# Adapterplatine_v1_2.net
KiCad netlist of a schematic drawn in EAGLE
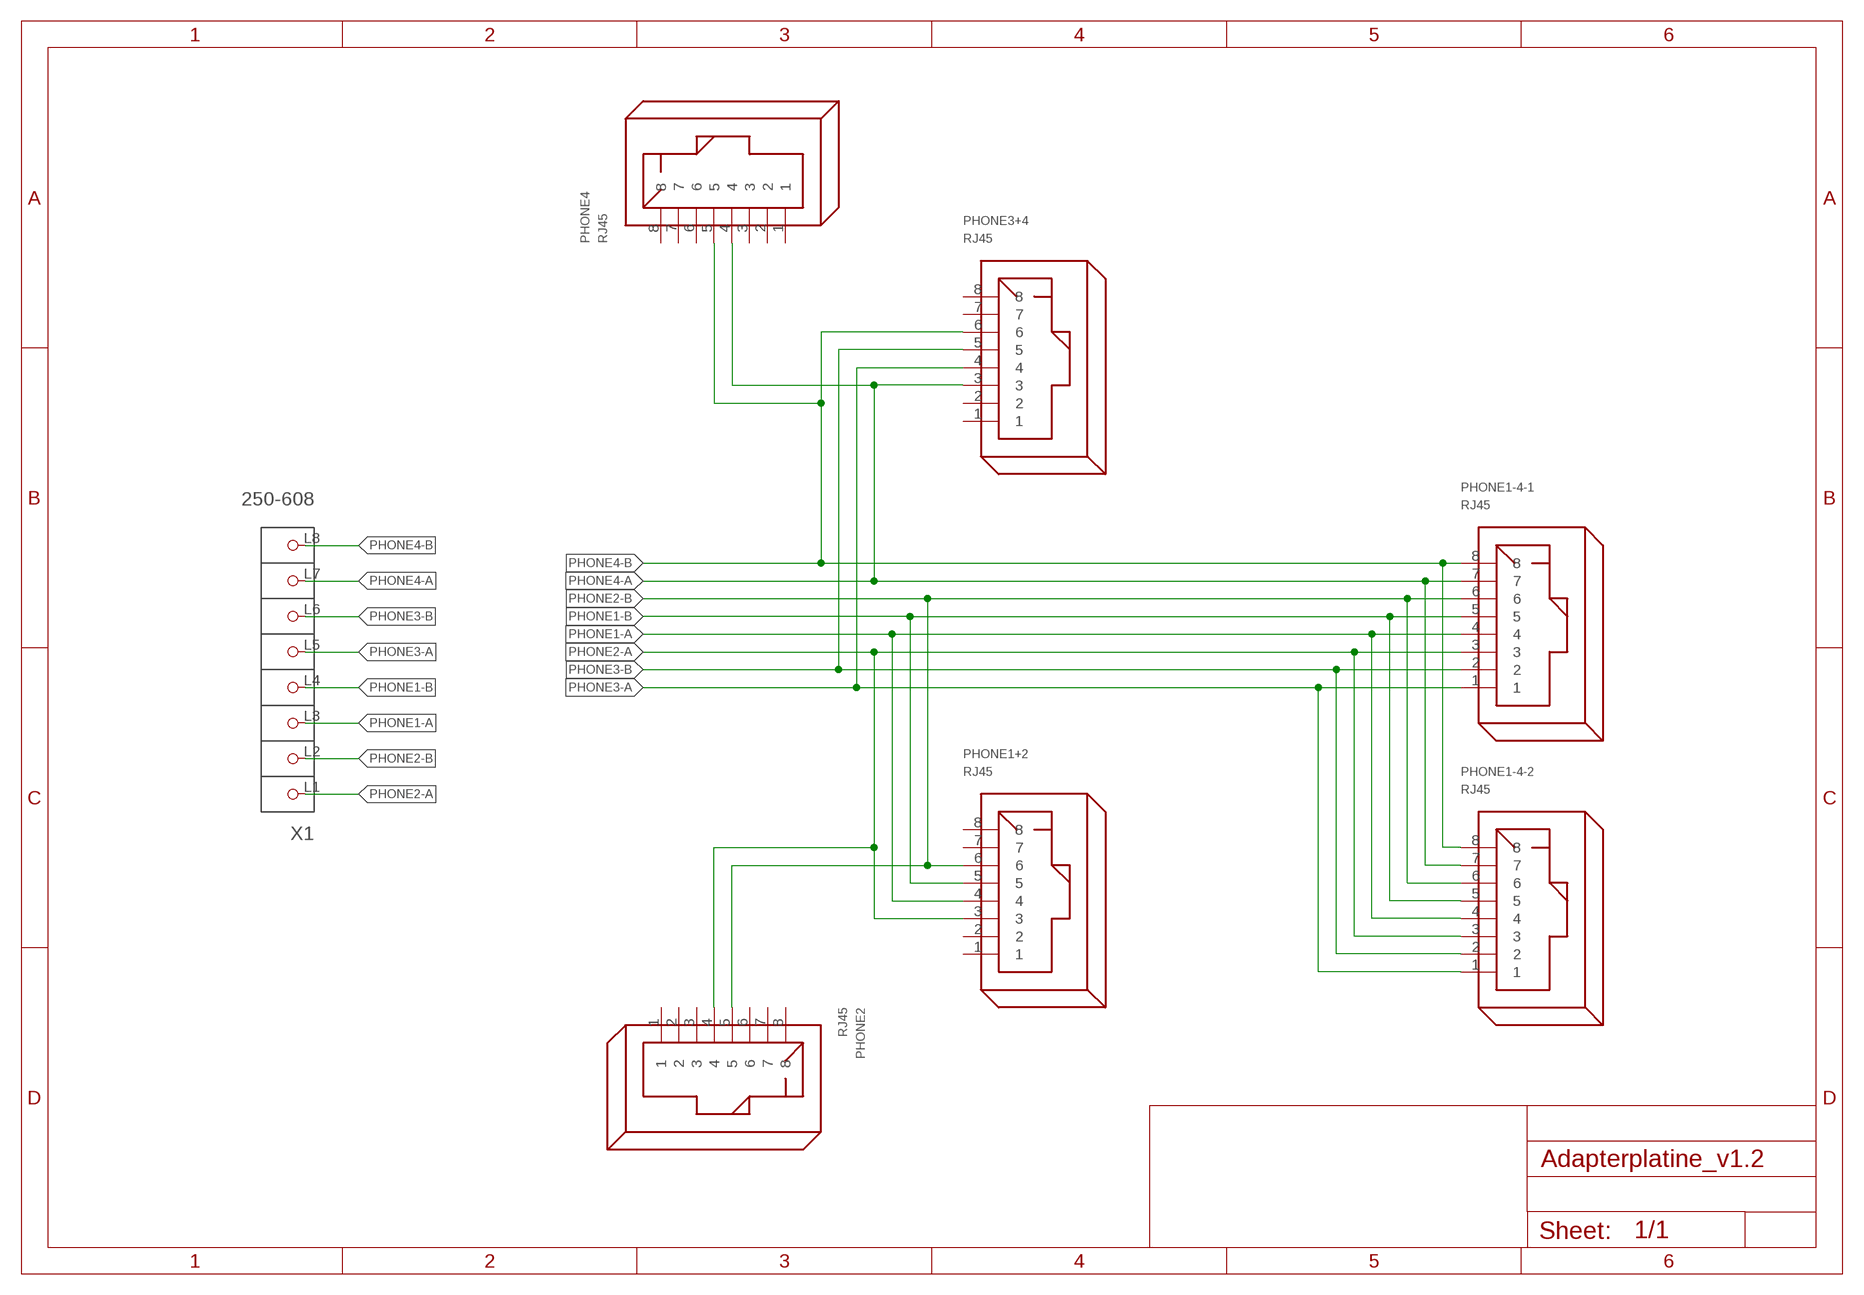
[diagram p0: schematic, sheet 1]

(export (version "E")
  (design (tool "Eeschema 10.0.6"))
  (components
    (comp (ref "PHONE1+2")
      (value "RJ45")
      (footprint "eagle-import:RJ45")
      (libsource (lib "eagle-import") (part "RJ45"))
    )
    (comp (ref "PHONE1-4-1")
      (value "RJ45")
      (footprint "eagle-import:RJ45")
      (libsource (lib "eagle-import") (part "RJ45"))
    )
    (comp (ref "PHONE1-4-2")
      (value "RJ45")
      (footprint "eagle-import:RJ45")
      (libsource (lib "eagle-import") (part "RJ45"))
    )
    (comp (ref "PHONE2")
      (value "RJ45")
      (footprint "eagle-import:RJ45")
      (libsource (lib "eagle-import") (part "RJ45"))
    )
    (comp (ref "PHONE3+4")
      (value "RJ45")
      (footprint "eagle-import:RJ45")
      (libsource (lib "eagle-import") (part "RJ45"))
    )
    (comp (ref "PHONE4")
      (value "RJ45")
      (footprint "eagle-import:RJ45")
      (libsource (lib "eagle-import") (part "RJ45"))
    )
    (comp (ref "X1")
      (value "250-608")
      (footprint "eagle-import:P-250-608")
      (libsource (lib "eagle-import") (part "250-608"))
    )
  )
  (nets
    (net (code "1") (name "PHONE1-A") (class "Default")
      (node (ref "PHONE1+2") (pin "4") (pinfunction "4_4") (pintype "bidirectional"))
      (node (ref "PHONE1-4-1") (pin "4") (pinfunction "4_4") (pintype "bidirectional"))
      (node (ref "PHONE1-4-2") (pin "4") (pinfunction "4_4") (pintype "bidirectional"))
      (node (ref "X1") (pin "L3") (pinfunction "P3_L3") (pintype "bidirectional"))
    )
    (net (code "2") (name "PHONE1-B") (class "Default")
      (node (ref "PHONE1+2") (pin "5") (pinfunction "5_5") (pintype "bidirectional"))
      (node (ref "PHONE1-4-1") (pin "5") (pinfunction "5_5") (pintype "bidirectional"))
      (node (ref "PHONE1-4-2") (pin "5") (pinfunction "5_5") (pintype "bidirectional"))
      (node (ref "X1") (pin "L4") (pinfunction "P4_L4") (pintype "bidirectional"))
    )
    (net (code "3") (name "PHONE2-A") (class "Default")
      (node (ref "PHONE1+2") (pin "3") (pinfunction "3_3") (pintype "bidirectional"))
      (node (ref "PHONE1-4-1") (pin "3") (pinfunction "3_3") (pintype "bidirectional"))
      (node (ref "PHONE1-4-2") (pin "3") (pinfunction "3_3") (pintype "bidirectional"))
      (node (ref "PHONE2") (pin "4") (pinfunction "4_4") (pintype "bidirectional"))
      (node (ref "X1") (pin "L1") (pinfunction "P1_L1") (pintype "bidirectional"))
    )
    (net (code "4") (name "PHONE2-B") (class "Default")
      (node (ref "PHONE1+2") (pin "6") (pinfunction "6_6") (pintype "bidirectional"))
      (node (ref "PHONE1-4-1") (pin "6") (pinfunction "6_6") (pintype "bidirectional"))
      (node (ref "PHONE1-4-2") (pin "6") (pinfunction "6_6") (pintype "bidirectional"))
      (node (ref "PHONE2") (pin "5") (pinfunction "5_5") (pintype "bidirectional"))
      (node (ref "X1") (pin "L2") (pinfunction "P2_L2") (pintype "bidirectional"))
    )
    (net (code "5") (name "PHONE3-A") (class "Default")
      (node (ref "PHONE1-4-1") (pin "1") (pinfunction "1_1") (pintype "bidirectional"))
      (node (ref "PHONE1-4-2") (pin "1") (pinfunction "1_1") (pintype "bidirectional"))
      (node (ref "PHONE3+4") (pin "4") (pinfunction "4_4") (pintype "bidirectional"))
      (node (ref "X1") (pin "L5") (pinfunction "P5_L5") (pintype "bidirectional"))
    )
    (net (code "6") (name "PHONE3-B") (class "Default")
      (node (ref "PHONE1-4-1") (pin "2") (pinfunction "2_2") (pintype "bidirectional"))
      (node (ref "PHONE1-4-2") (pin "2") (pinfunction "2_2") (pintype "bidirectional"))
      (node (ref "PHONE3+4") (pin "5") (pinfunction "5_5") (pintype "bidirectional"))
      (node (ref "X1") (pin "L6") (pinfunction "P6_L6") (pintype "bidirectional"))
    )
    (net (code "7") (name "PHONE4-A") (class "Default")
      (node (ref "PHONE1-4-1") (pin "7") (pinfunction "7_7") (pintype "bidirectional"))
      (node (ref "PHONE1-4-2") (pin "7") (pinfunction "7_7") (pintype "bidirectional"))
      (node (ref "PHONE3+4") (pin "3") (pinfunction "3_3") (pintype "bidirectional"))
      (node (ref "PHONE4") (pin "4") (pinfunction "4_4") (pintype "bidirectional"))
      (node (ref "X1") (pin "L7") (pinfunction "P7_L7") (pintype "bidirectional"))
    )
    (net (code "8") (name "PHONE4-B") (class "Default")
      (node (ref "PHONE1-4-1") (pin "8") (pinfunction "8_8") (pintype "bidirectional"))
      (node (ref "PHONE1-4-2") (pin "8") (pinfunction "8_8") (pintype "bidirectional"))
      (node (ref "PHONE3+4") (pin "6") (pinfunction "6_6") (pintype "bidirectional"))
      (node (ref "PHONE4") (pin "5") (pinfunction "5_5") (pintype "bidirectional"))
      (node (ref "X1") (pin "L8") (pinfunction "P8_L8") (pintype "bidirectional"))
    )
    (net (code "9") (name "unconnected-(PHONE1+2-Pad1)") (class "Default")
      (node (ref "PHONE1+2") (pin "1") (pinfunction "1_1") (pintype "bidirectional"))
    )
    (net (code "10") (name "unconnected-(PHONE1+2-Pad2)") (class "Default")
      (node (ref "PHONE1+2") (pin "2") (pinfunction "2_2") (pintype "bidirectional"))
    )
    (net (code "11") (name "unconnected-(PHONE1+2-Pad7)") (class "Default")
      (node (ref "PHONE1+2") (pin "7") (pinfunction "7_7") (pintype "bidirectional"))
    )
    (net (code "12") (name "unconnected-(PHONE1+2-Pad8)") (class "Default")
      (node (ref "PHONE1+2") (pin "8") (pinfunction "8_8") (pintype "bidirectional"))
    )
    (net (code "13") (name "unconnected-(PHONE2-Pad1)") (class "Default")
      (node (ref "PHONE2") (pin "1") (pinfunction "1_1") (pintype "bidirectional"))
    )
    (net (code "14") (name "unconnected-(PHONE2-Pad2)") (class "Default")
      (node (ref "PHONE2") (pin "2") (pinfunction "2_2") (pintype "bidirectional"))
    )
    (net (code "15") (name "unconnected-(PHONE2-Pad3)") (class "Default")
      (node (ref "PHONE2") (pin "3") (pinfunction "3_3") (pintype "bidirectional"))
    )
    (net (code "16") (name "unconnected-(PHONE2-Pad6)") (class "Default")
      (node (ref "PHONE2") (pin "6") (pinfunction "6_6") (pintype "bidirectional"))
    )
    (net (code "17") (name "unconnected-(PHONE2-Pad7)") (class "Default")
      (node (ref "PHONE2") (pin "7") (pinfunction "7_7") (pintype "bidirectional"))
    )
    (net (code "18") (name "unconnected-(PHONE2-Pad8)") (class "Default")
      (node (ref "PHONE2") (pin "8") (pinfunction "8_8") (pintype "bidirectional"))
    )
    (net (code "19") (name "unconnected-(PHONE3+4-Pad1)") (class "Default")
      (node (ref "PHONE3+4") (pin "1") (pinfunction "1_1") (pintype "bidirectional"))
    )
    (net (code "20") (name "unconnected-(PHONE3+4-Pad2)") (class "Default")
      (node (ref "PHONE3+4") (pin "2") (pinfunction "2_2") (pintype "bidirectional"))
    )
    (net (code "21") (name "unconnected-(PHONE3+4-Pad7)") (class "Default")
      (node (ref "PHONE3+4") (pin "7") (pinfunction "7_7") (pintype "bidirectional"))
    )
    (net (code "22") (name "unconnected-(PHONE3+4-Pad8)") (class "Default")
      (node (ref "PHONE3+4") (pin "8") (pinfunction "8_8") (pintype "bidirectional"))
    )
    (net (code "23") (name "unconnected-(PHONE4-Pad1)") (class "Default")
      (node (ref "PHONE4") (pin "1") (pinfunction "1_1") (pintype "bidirectional"))
    )
    (net (code "24") (name "unconnected-(PHONE4-Pad2)") (class "Default")
      (node (ref "PHONE4") (pin "2") (pinfunction "2_2") (pintype "bidirectional"))
    )
    (net (code "25") (name "unconnected-(PHONE4-Pad3)") (class "Default")
      (node (ref "PHONE4") (pin "3") (pinfunction "3_3") (pintype "bidirectional"))
    )
    (net (code "26") (name "unconnected-(PHONE4-Pad6)") (class "Default")
      (node (ref "PHONE4") (pin "6") (pinfunction "6_6") (pintype "bidirectional"))
    )
    (net (code "27") (name "unconnected-(PHONE4-Pad7)") (class "Default")
      (node (ref "PHONE4") (pin "7") (pinfunction "7_7") (pintype "bidirectional"))
    )
    (net (code "28") (name "unconnected-(PHONE4-Pad8)") (class "Default")
      (node (ref "PHONE4") (pin "8") (pinfunction "8_8") (pintype "bidirectional"))
    )
  )
)
